# RFM69HCW_Atmega328PB_Schematic.net
KiCad netlist of a schematic drawn in Altium Designer
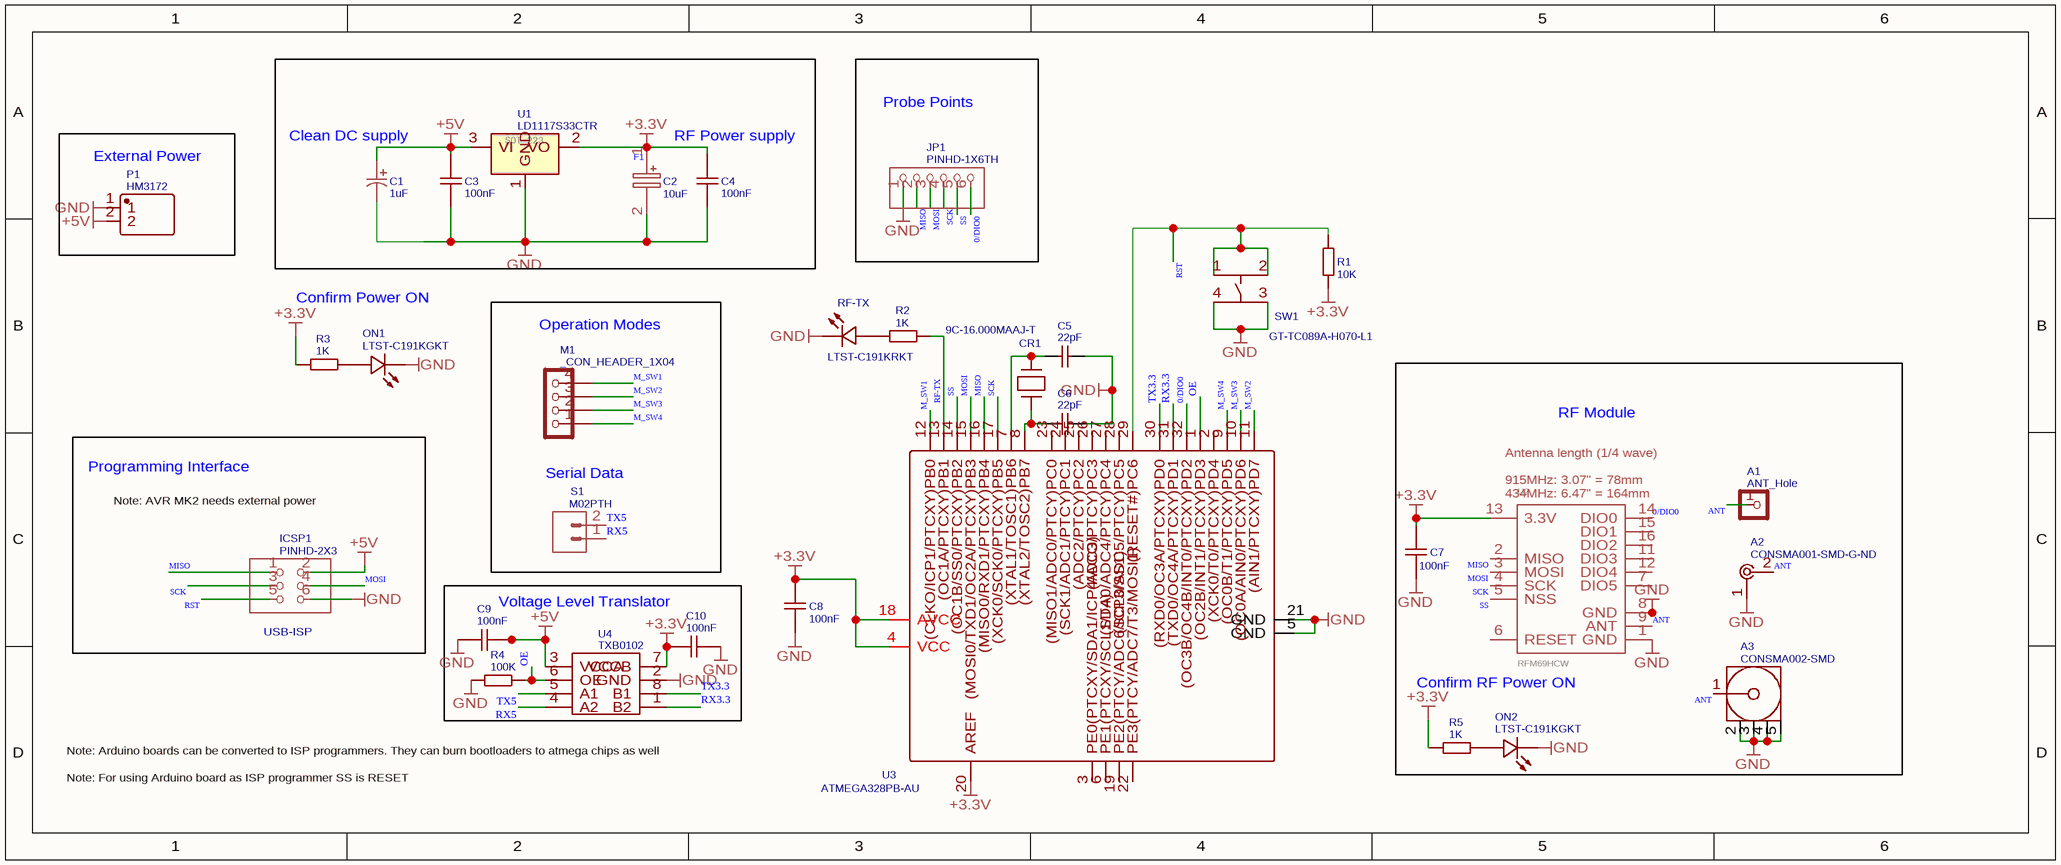
[diagram p0: RFM69HCW_Atmega328PB_Schematic.schdoc]

(export (version "E")
  (design (tool "Eeschema 10.0.6"))
  (components
    (comp (ref "A1")
      (value "ANT_Hole")
      (fields (field (name "CONTRIBUTOR") "DangerousPrototype"))
      (libsource (lib "altium-import") (part "root_0_ANT_Hole_"))
    )
    (comp (ref "A2")
      (value "CONSMA001-SMD-G-ND")
      (fields (field (name "CONTRIBUTOR") "Ron Childress"))
      (libsource (lib "altium-import") (part "root_0_CONSMA001-SMD-G-ND_"))
    )
    (comp (ref "A3")
      (value "CONSMA002-SMD")
      (description "SMA Female Right Angle Surface Mount Connector")
      (libsource (lib "altium-import") (part "root_0_CONSMA002-SMD_"))
    )
    (comp (ref "C1")
      (value "1uF")
      (fields (field (name "CONTRIBUTOR") "tkowalski"))
      (libsource (lib "altium-import") (part "root_3_1uF_"))
    )
    (comp (ref "C2")
      (value "10uF")
      (fields (field (name "CONTRIBUTOR") "tmanabc123"))
      (libsource (lib "altium-import") (part "root_3_10uF_"))
    )
    (comp (ref "C3")
      (value "100nF")
      (fields
        (field (name "BOM_SUPPLIER PART") "C599655")
        (field (name "BOM_MANUFACTURER PART") "C0603C104M5RAC7867")
        (field (name "CONTRIBUTOR") "LCSC")
      )
      (libsource (lib "altium-import") (part "root_1_100nF_"))
    )
    (comp (ref "C4")
      (value "100nF")
      (fields
        (field (name "BOM_SUPPLIER PART") "C599655")
        (field (name "BOM_MANUFACTURER PART") "C0603C104M5RAC7867")
        (field (name "CONTRIBUTOR") "LCSC")
      )
      (libsource (lib "altium-import") (part "root_1_100nF_"))
    )
    (comp (ref "C5")
      (value "22pF")
      (fields
        (field (name "BOM_MANUFACTURER PART") "CL10C220JB8NNNC")
        (field (name "BOM_SUPPLIER PART") "C1653")
      )
      (libsource (lib "altium-import") (part "root_0_22pF_"))
    )
    (comp (ref "C6")
      (value "22pF")
      (fields
        (field (name "BOM_MANUFACTURER PART") "CL10C220JB8NNNC")
        (field (name "BOM_SUPPLIER PART") "C1653")
      )
      (libsource (lib "altium-import") (part "root_0_22pF_"))
    )
    (comp (ref "C7")
      (value "100nF")
      (fields
        (field (name "BOM_SUPPLIER PART") "C599655")
        (field (name "BOM_MANUFACTURER PART") "C0603C104M5RAC7867")
        (field (name "CONTRIBUTOR") "LCSC")
      )
      (libsource (lib "altium-import") (part "root_1_100nF_"))
    )
    (comp (ref "C8")
      (value "100nF")
      (fields
        (field (name "BOM_SUPPLIER PART") "C599655")
        (field (name "BOM_MANUFACTURER PART") "C0603C104M5RAC7867")
        (field (name "CONTRIBUTOR") "LCSC")
      )
      (libsource (lib "altium-import") (part "root_1_100nF_"))
    )
    (comp (ref "C9")
      (value "100nF")
      (fields
        (field (name "BOM_SUPPLIER PART") "C599655")
        (field (name "BOM_MANUFACTURER PART") "C0603C104M5RAC7867")
        (field (name "CONTRIBUTOR") "LCSC")
      )
      (libsource (lib "altium-import") (part "root_0_100nF_"))
    )
    (comp (ref "C10")
      (value "100nF")
      (fields
        (field (name "BOM_SUPPLIER PART") "C599655")
        (field (name "BOM_MANUFACTURER PART") "C0603C104M5RAC7867")
        (field (name "CONTRIBUTOR") "LCSC")
      )
      (libsource (lib "altium-import") (part "root_2_100nF_"))
    )
    (comp (ref "CR1")
      (value "9C-16.000MAAJ-T")
      (fields (field (name "CONTRIBUTOR") "Utsav Trivedi"))
      (libsource (lib "altium-import") (part "root_1_9C-16.000MAAJ-T_"))
    )
    (comp (ref "ICSP1")
      (value "PINHD-2X3")
      (fields (field (name "CONTRIBUTOR") "Utsav Trivedi"))
      (libsource (lib "altium-import") (part "root_0_PINHD-2X3_"))
    )
    (comp (ref "JP1")
      (value "PINHD-1X6TH")
      (fields (field (name "CONTRIBUTOR") "Utsav Trivedi"))
      (libsource (lib "altium-import") (part "root_1_PINHD-1X6TH_"))
    )
    (comp (ref "M1")
      (value "_CON_HEADER_1X04")
      (fields (field (name "CONTRIBUTOR") "DangerousPrototype"))
      (libsource (lib "altium-import") (part "root_0__CON_HEADER_1X04_"))
    )
    (comp (ref "ON1")
      (value "LTST-C191KGKT")
      (fields (field (name "BOM_SUPPLIER PART") "C125098") (field (name "CONTRIBUTOR") "LCSC"))
      (libsource (lib "altium-import") (part "root_2_LTST-C191KGKT_"))
    )
    (comp (ref "ON2")
      (value "LTST-C191KGKT")
      (fields (field (name "BOM_SUPPLIER PART") "C125098") (field (name "CONTRIBUTOR") "LCSC"))
      (libsource (lib "altium-import") (part "root_2_LTST-C191KGKT_"))
    )
    (comp (ref "P1")
      (value "HM3172")
      (fields (field (name "CONTRIBUTOR") "EdoKuipers"))
      (libsource (lib "altium-import") (part "root_0_HM3172_"))
    )
    (comp (ref "R1")
      (value "10K")
      (fields
        (field (name "BOM_SUPPLIER PART") "C224640")
        (field (name "BOM_MANUFACTURER PART") "MCR03ERTF1002")
        (field (name "CONTRIBUTOR") "LCSC")
      )
      (libsource (lib "altium-import") (part "root_1_10K_"))
    )
    (comp (ref "R2")
      (value "1K")
      (fields
        (field (name "BOM_SUPPLIER PART") "C118155")
        (field (name "BOM_MANUFACTURER PART") "ERJ-3EKF1001V")
        (field (name "CONTRIBUTOR") "LCSC")
      )
      (libsource (lib "altium-import") (part "root_0_1K_"))
    )
    (comp (ref "R3")
      (value "1K")
      (fields
        (field (name "BOM_SUPPLIER PART") "C118155")
        (field (name "BOM_MANUFACTURER PART") "ERJ-3EKF1001V")
        (field (name "CONTRIBUTOR") "LCSC")
      )
      (libsource (lib "altium-import") (part "root_0_1K_"))
    )
    (comp (ref "R4")
      (value "100K")
      (fields
        (field (name "BOM_SUPPLIER PART") "C14675")
        (field (name "BOM_MANUFACTURER PART") "v")
        (field (name "CONTRIBUTOR") "LCSC")
      )
      (libsource (lib "altium-import") (part "root_2_100K_"))
    )
    (comp (ref "R5")
      (value "1K")
      (fields
        (field (name "BOM_SUPPLIER PART") "C118155")
        (field (name "BOM_MANUFACTURER PART") "ERJ-3EKF1001V")
        (field (name "CONTRIBUTOR") "LCSC")
      )
      (libsource (lib "altium-import") (part "root_0_1K_"))
    )
    (comp (ref "RF-TX")
      (value "LTST-C191KRKT")
      (fields (field (name "BOM_SUPPLIER PART") "C125099") (field (name "CONTRIBUTOR") "LCSC"))
      (libsource (lib "altium-import") (part "root_0_LTST-C191KRKT_"))
    )
    (comp (ref "S1")
      (value "M02PTH")
      (fields (field (name "CONTRIBUTOR") "Utsav Trivedi"))
      (libsource (lib "altium-import") (part "root_0_M02PTH_"))
    )
    (comp (ref "SW1")
      (value "GT-TC089A-H070-L1")
      (fields (field (name "BOM_SUPPLIER PART") "C778179") (field (name "CONTRIBUTOR") "LCSC"))
      (libsource (lib "altium-import") (part "root_0_GT-TC089A-H070-L1_"))
    )
    (comp (ref "U1")
      (value "LD1117S33CTR")
      (fields (field (name "CONTRIBUTOR") "Philip Dale"))
      (libsource (lib "altium-import") (part "root_0_LD1117S33CTR_"))
    )
    (comp (ref "U2") (value "RFM69HCW") (libsource (lib "altium-import") (part "root_0_RFM69HCW_")))
    (comp (ref "U3")
      (value "ATMEGA328PB-AU")
      (fields (field (name "BOM_SUPPLIER PART") "C132230") (field (name "CONTRIBUTOR") "LCSC"))
      (libsource (lib "altium-import") (part "root_1_ATMEGA328PB-AU_"))
    )
    (comp (ref "U4")
      (value "TXB0102")
      (fields
        (field (name "BOM_MANUFACTURER PART") "TXB0102DCUR")
        (field (name "CONTRIBUTOR") "Prince Bahoumina")
      )
      (libsource (lib "altium-import") (part "root_0_TXB0102_"))
    )
  )
  (nets
    (net (code "1") (name "+3.3V") (class "Default")
      (node (ref "C10") (pin "2") (pinfunction "2_2") (pintype "passive"))
      (node (ref "C2") (pin "1") (pinfunction "+_1") (pintype "passive"))
      (node (ref "C4") (pin "2") (pinfunction "2_2") (pintype "passive"))
      (node (ref "C7") (pin "2") (pinfunction "2_2") (pintype "passive"))
      (node (ref "C8") (pin "2") (pinfunction "2_2") (pintype "passive"))
      (node (ref "R1") (pin "1") (pinfunction "1_1") (pintype "passive"))
      (node (ref "R3") (pin "1") (pinfunction "1_1") (pintype "passive"))
      (node (ref "R5") (pin "1") (pinfunction "1_1") (pintype "passive"))
      (node (ref "U1") (pin "2") (pinfunction "VO_2") (pintype "passive"))
      (node (ref "U2") (pin "13") (pinfunction "3.3V_13") (pintype "passive"))
      (node (ref "U3") (pin "18") (pinfunction "AVCC_18") (pintype "passive"))
      (node (ref "U3") (pin "20") (pinfunction "AREF_20") (pintype "passive"))
      (node (ref "U3") (pin "4") (pinfunction "VCC_4") (pintype "passive"))
      (node (ref "U4") (pin "7") (pinfunction "VCCB_7") (pintype "passive"))
    )
    (net (code "2") (name "+5V") (class "Default")
      (node (ref "C1") (pin "1") (pinfunction "1_1") (pintype "passive"))
      (node (ref "C3") (pin "2") (pinfunction "2_2") (pintype "passive"))
      (node (ref "C9") (pin "2") (pinfunction "2_2") (pintype "passive"))
      (node (ref "ICSP1") (pin "2") (pinfunction "2_2") (pintype "passive"))
      (node (ref "P1") (pin "2") (pinfunction "2_2") (pintype "passive"))
      (node (ref "U1") (pin "3") (pinfunction "VI_3") (pintype "passive"))
      (node (ref "U4") (pin "3") (pinfunction "VCCA_3") (pintype "passive"))
    )
    (net (code "3") (name "/0{slash}DIO0") (class "Default")
      (node (ref "JP1") (pin "6") (pinfunction "6_6") (pintype "passive"))
      (node (ref "U2") (pin "14") (pinfunction "DIO0_14") (pintype "passive"))
      (node (ref "U3") (pin "32") (pinfunction "(OC3B/OC4B/INT0/PTCXY)PD2_32") (pintype "passive"))
    )
    (net (code "4") (name "/ANT") (class "Default")
      (node (ref "A1") (pin "1") (pinfunction "1_1") (pintype "passive"))
      (node (ref "A2") (pin "2") (pintype "passive"))
      (node (ref "A3") (pin "1") (pinfunction "Signal_1") (pintype "passive"))
      (node (ref "U2") (pin "9") (pinfunction "ANT_9") (pintype "passive"))
    )
    (net (code "5") (name "/MISO") (class "Default")
      (node (ref "ICSP1") (pin "1") (pinfunction "1_1") (pintype "passive"))
      (node (ref "JP1") (pin "2") (pinfunction "2_2") (pintype "passive"))
      (node (ref "U2") (pin "2") (pinfunction "MISO_2") (pintype "passive"))
      (node (ref "U3") (pin "16") (pinfunction "(MISO0/RXD1/PTCXY)PB4_16") (pintype "passive"))
    )
    (net (code "6") (name "/MOSI") (class "Default")
      (node (ref "ICSP1") (pin "4") (pinfunction "4_4") (pintype "passive"))
      (node (ref "JP1") (pin "3") (pinfunction "3_3") (pintype "passive"))
      (node (ref "U2") (pin "3") (pinfunction "MOSI_3") (pintype "passive"))
      (node (ref "U3") (pin "15") (pinfunction "(MOSI0/TXD1/OC2A/PTCXY)PB3_15") (pintype "passive"))
    )
    (net (code "7") (name "/M_SW1") (class "Default")
      (node (ref "M1") (pin "4") (pinfunction "4_4") (pintype "passive"))
      (node (ref "U3") (pin "12") (pinfunction "(CLKO/ICP1/PTCXY)PB0_12") (pintype "passive"))
    )
    (net (code "8") (name "/M_SW2") (class "Default")
      (node (ref "M1") (pin "3") (pinfunction "3_3") (pintype "passive"))
      (node (ref "U3") (pin "11") (pinfunction "(AIN1/PTCXY)PD7_11") (pintype "passive"))
    )
    (net (code "9") (name "/M_SW3") (class "Default")
      (node (ref "M1") (pin "2") (pinfunction "2_2") (pintype "passive"))
      (node (ref "U3") (pin "10") (pinfunction "(OC0A/AIN0/PTCXY)PD6_10") (pintype "passive"))
    )
    (net (code "10") (name "/M_SW4") (class "Default")
      (node (ref "M1") (pin "1") (pinfunction "1_1") (pintype "passive"))
      (node (ref "U3") (pin "9") (pinfunction "(OC0B/T1/PTCXY)PD5_9") (pintype "passive"))
    )
    (net (code "11") (name "/OE") (class "Default")
      (node (ref "R4") (pin "1") (pinfunction "1_1") (pintype "passive"))
      (node (ref "U3") (pin "1") (pinfunction "(OC2B/INT1/PTCXY)PD3_1") (pintype "passive"))
      (node (ref "U4") (pin "6") (pinfunction "OE_6") (pintype "passive"))
    )
    (net (code "12") (name "/RF-TX") (class "Default")
      (node (ref "R2") (pin "2") (pinfunction "2_2") (pintype "passive"))
      (node (ref "U3") (pin "13") (pinfunction "(OC1A/PTCXY)PB1_13") (pintype "passive"))
    )
    (net (code "13") (name "/RST") (class "Default")
      (node (ref "ICSP1") (pin "5") (pinfunction "5_5") (pintype "passive"))
      (node (ref "R1") (pin "2") (pinfunction "2_2") (pintype "passive"))
      (node (ref "SW1") (pin "1") (pinfunction "1_1") (pintype "passive"))
      (node (ref "SW1") (pin "2") (pinfunction "2_2") (pintype "passive"))
      (node (ref "U3") (pin "29") (pinfunction "(RESET#)PC6_29") (pintype "passive"))
    )
    (net (code "14") (name "/RX3.3") (class "Default")
      (node (ref "U3") (pin "31") (pinfunction "(TXD0/OC4A/PTCXY)PD1_31") (pintype "passive"))
      (node (ref "U4") (pin "1") (pinfunction "B2_1") (pintype "passive"))
    )
    (net (code "15") (name "/RX5") (class "Default")
      (node (ref "S1") (pin "1") (pinfunction "1_1") (pintype "passive"))
      (node (ref "U4") (pin "4") (pinfunction "A2_4") (pintype "passive"))
    )
    (net (code "16") (name "/SCK") (class "Default")
      (node (ref "ICSP1") (pin "3") (pinfunction "3_3") (pintype "passive"))
      (node (ref "JP1") (pin "4") (pinfunction "4_4") (pintype "passive"))
      (node (ref "U2") (pin "4") (pinfunction "SCK_4") (pintype "passive"))
      (node (ref "U3") (pin "17") (pinfunction "(XCK0/SCK0/PTCXY)PB5_17") (pintype "passive"))
    )
    (net (code "17") (name "/SS") (class "Default")
      (node (ref "JP1") (pin "5") (pinfunction "5_5") (pintype "passive"))
      (node (ref "U2") (pin "5") (pinfunction "NSS_5") (pintype "passive"))
      (node (ref "U3") (pin "14") (pinfunction "(OC1B/SS0/PTCXY)PB2_14") (pintype "passive"))
    )
    (net (code "18") (name "/TX3.3") (class "Default")
      (node (ref "U3") (pin "30") (pinfunction "(RXD0/OC3A/PTCXY)PD0_30") (pintype "passive"))
      (node (ref "U4") (pin "8") (pinfunction "B1_8") (pintype "passive"))
    )
    (net (code "19") (name "/TX5") (class "Default")
      (node (ref "S1") (pin "2") (pinfunction "2_2") (pintype "passive"))
      (node (ref "U4") (pin "5") (pinfunction "A1_5") (pintype "passive"))
    )
    (net (code "20") (name "GND") (class "Default")
      (node (ref "A2") (pin "1") (pintype "passive"))
      (node (ref "A3") (pin "2") (pinfunction "GND_2") (pintype "passive"))
      (node (ref "A3") (pin "3") (pinfunction "GND_3") (pintype "passive"))
      (node (ref "A3") (pin "4") (pinfunction "GND_4") (pintype "passive"))
      (node (ref "A3") (pin "5") (pinfunction "GND_5") (pintype "passive"))
      (node (ref "C1") (pin "2") (pinfunction "2_2") (pintype "passive"))
      (node (ref "C10") (pin "1") (pinfunction "1_1") (pintype "passive"))
      (node (ref "C2") (pin "2") (pinfunction "-_2") (pintype "passive"))
      (node (ref "C3") (pin "1") (pinfunction "1_1") (pintype "passive"))
      (node (ref "C4") (pin "1") (pinfunction "1_1") (pintype "passive"))
      (node (ref "C5") (pin "2") (pinfunction "2_2") (pintype "passive"))
      (node (ref "C6") (pin "2") (pinfunction "2_2") (pintype "passive"))
      (node (ref "C7") (pin "1") (pinfunction "1_1") (pintype "passive"))
      (node (ref "C8") (pin "1") (pinfunction "1_1") (pintype "passive"))
      (node (ref "C9") (pin "1") (pinfunction "1_1") (pintype "passive"))
      (node (ref "ICSP1") (pin "6") (pinfunction "6_6") (pintype "passive"))
      (node (ref "JP1") (pin "1") (pinfunction "1_1") (pintype "passive"))
      (node (ref "ON1") (pin "1") (pinfunction "-_1") (pintype "passive"))
      (node (ref "ON2") (pin "1") (pinfunction "-_1") (pintype "passive"))
      (node (ref "P1") (pin "1") (pinfunction "1_1") (pintype "passive"))
      (node (ref "R4") (pin "2") (pinfunction "2_2") (pintype "passive"))
      (node (ref "RF-TX") (pin "1") (pinfunction "-_1") (pintype "passive"))
      (node (ref "SW1") (pin "3") (pinfunction "3_3") (pintype "passive"))
      (node (ref "SW1") (pin "4") (pinfunction "4_4") (pintype "passive"))
      (node (ref "U1") (pin "1") (pinfunction "GND_1") (pintype "passive"))
      (node (ref "U2") (pin "1") (pinfunction "GND_1") (pintype "passive"))
      (node (ref "U2") (pin "10") (pinfunction "GND_10") (pintype "passive"))
      (node (ref "U2") (pin "8") (pinfunction "GND_8") (pintype "passive"))
      (node (ref "U3") (pin "21") (pinfunction "GND_21") (pintype "passive"))
      (node (ref "U3") (pin "5") (pinfunction "GND_5") (pintype "passive"))
      (node (ref "U4") (pin "2") (pinfunction "GND_2") (pintype "passive"))
    )
    (net (code "21") (name "Net-(ON1-+)") (class "Default")
      (node (ref "ON1") (pin "2") (pinfunction "+_2") (pintype "passive"))
      (node (ref "R3") (pin "2") (pinfunction "2_2") (pintype "passive"))
    )
    (net (code "22") (name "Net-(ON2-+)") (class "Default")
      (node (ref "ON2") (pin "2") (pinfunction "+_2") (pintype "passive"))
      (node (ref "R5") (pin "2") (pinfunction "2_2") (pintype "passive"))
    )
    (net (code "23") (name "Net-(RF-TX-+)") (class "Default")
      (node (ref "R2") (pin "1") (pinfunction "1_1") (pintype "passive"))
      (node (ref "RF-TX") (pin "2") (pinfunction "+_2") (pintype "passive"))
    )
    (net (code "24") (name "Net-(U3-(XTAL1{slash}TOSC1)PB6)") (class "Default")
      (node (ref "C5") (pin "1") (pinfunction "1_1") (pintype "passive"))
      (node (ref "CR1") (pin "2") (pinfunction "2_2") (pintype "passive"))
      (node (ref "U3") (pin "7") (pinfunction "(XTAL1/TOSC1)PB6_7") (pintype "passive"))
    )
    (net (code "25") (name "Net-(U3-(XTAL2{slash}TOSC2)PB7)") (class "Default")
      (node (ref "C6") (pin "1") (pinfunction "1_1") (pintype "passive"))
      (node (ref "CR1") (pin "1") (pinfunction "1_1") (pintype "passive"))
      (node (ref "U3") (pin "8") (pinfunction "(XTAL2/TOSC2)PB7_8") (pintype "passive"))
    )
    (net (code "26") (name "unconnected-(U2-DIO1-Pad15)") (class "Default")
      (node (ref "U2") (pin "15") (pinfunction "DIO1_15") (pintype "passive"))
    )
    (net (code "27") (name "unconnected-(U2-DIO2-Pad16)") (class "Default")
      (node (ref "U2") (pin "16") (pinfunction "DIO2_16") (pintype "passive"))
    )
    (net (code "28") (name "unconnected-(U2-DIO3-Pad11)") (class "Default")
      (node (ref "U2") (pin "11") (pinfunction "DIO3_11") (pintype "passive"))
    )
    (net (code "29") (name "unconnected-(U2-DIO4-Pad12)") (class "Default")
      (node (ref "U2") (pin "12") (pinfunction "DIO4_12") (pintype "passive"))
    )
    (net (code "30") (name "unconnected-(U2-DIO5-Pad7)") (class "Default")
      (node (ref "U2") (pin "7") (pinfunction "DIO5_7") (pintype "passive"))
    )
    (net (code "31") (name "unconnected-(U2-RESET-Pad6)") (class "Default")
      (node (ref "U2") (pin "6") (pinfunction "RESET_6") (pintype "passive"))
    )
    (net (code "32") (name "unconnected-(U3-(ADC2{slash}PTCY)PC2-Pad25)") (class "Default")
      (node (ref "U3") (pin "25") (pinfunction "(ADC2/PTCY)PC2_25") (pintype "passive"))
    )
    (net (code "33") (name "unconnected-(U3-(ADC3{slash}PTCY)PC3-Pad26)") (class "Default")
      (node (ref "U3") (pin "26") (pinfunction "(ADC3/PTCY)PC3_26") (pintype "passive"))
    )
    (net (code "34") (name "unconnected-(U3-(MISO1{slash}ADC0{slash}PTCY)PC0-Pad23)") (class "Default")
      (node (ref "U3") (pin "23") (pinfunction "(MISO1/ADC0/PTCY)PC0_23") (pintype "passive"))
    )
    (net (code "35") (name "unconnected-(U3-(SCK1{slash}ADC1{slash}PTCY)PC1-Pad24)") (class "Default")
      (node (ref "U3") (pin "24") (pinfunction "(SCK1/ADC1/PTCY)PC1_24") (pintype "passive"))
    )
    (net (code "36") (name "unconnected-(U3-(SCL0{slash}ADC5{slash}PTCY)PC5-Pad28)") (class "Default")
      (node (ref "U3") (pin "28") (pinfunction "(SCL0/ADC5/PTCY)PC5_28") (pintype "passive"))
    )
    (net (code "37") (name "unconnected-(U3-(SDA0{slash}ADC4{slash}PTCY)PC4-Pad27)") (class "Default")
      (node (ref "U3") (pin "27") (pinfunction "(SDA0/ADC4/PTCY)PC4_27") (pintype "passive"))
    )
    (net (code "38") (name "unconnected-(U3-(XCK0{slash}T0{slash}PTCXY)PD4-Pad2)") (class "Default")
      (node (ref "U3") (pin "2") (pinfunction "(XCK0/T0/PTCXY)PD4_2") (pintype "passive"))
    )
    (net (code "39") (name "unconnected-(U3-PE0(PTCXY{slash}SDA1{slash}ICP4{slash}ACO)-Pad3)") (class "Default")
      (node (ref "U3") (pin "3") (pinfunction "PE0(PTCXY/SDA1/ICP4/ACO)_3") (pintype "passive"))
    )
    (net (code "40") (name "unconnected-(U3-PE1(PTCXY{slash}SCL1{slash}T4)-Pad6)") (class "Default")
      (node (ref "U3") (pin "6") (pinfunction "PE1(PTCXY/SCL1/T4)_6") (pintype "passive"))
    )
    (net (code "41") (name "unconnected-(U3-PE2(PTCY{slash}ADC6{slash}ICP3{slash}SS1)-Pad19)") (class "Default")
      (node (ref "U3") (pin "19") (pinfunction "PE2(PTCY/ADC6/ICP3/SS1)_19") (pintype "passive"))
    )
    (net (code "42") (name "unconnected-(U3-PE3(PTCY{slash}ADC7{slash}T3{slash}MOSI1)-Pad22)") (class "Default")
      (node (ref "U3") (pin "22") (pinfunction "PE3(PTCY/ADC7/T3/MOSI1)_22") (pintype "passive"))
    )
  )
)
